# radio-a.net
KiCad netlist of a schematic drawn in Altium Designer
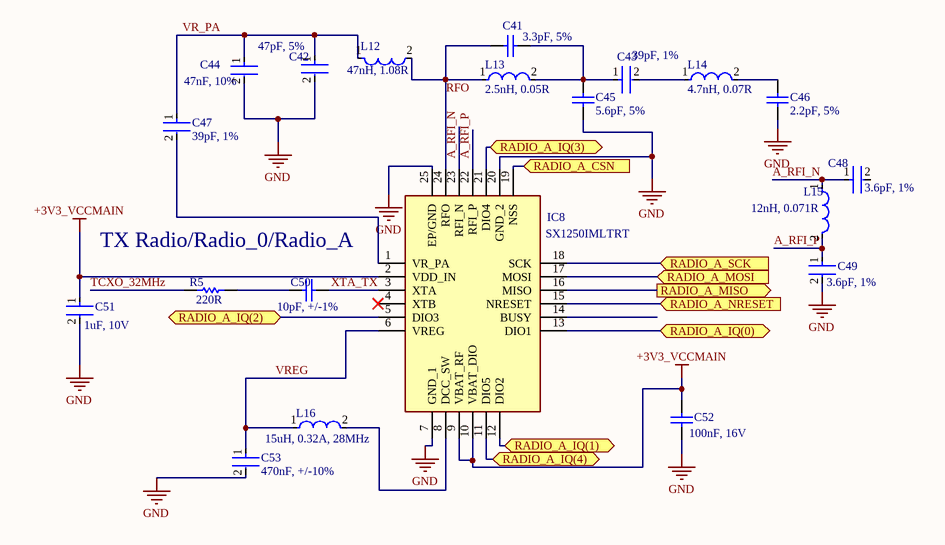
[diagram p0: radio-a.SchDoc]

(export (version "E")
  (design (tool "Eeschema 10.0.6"))
  (components
    (comp (ref "C41")
      (value "3.3pF, 5%")
      (footprint "CAPC0603(1608)100_L")
      (description "CAP 3.3pF 50V ±5% 0603 (1608 Metric) Thickness 1mm SMD")
      (fields (field (name "TOLERANCE") "Â±5%"))
      (libsource (lib "Altium Content Vault") (part "CAP"))
    )
    (comp (ref "C42")
      (value "47pF, 5%")
      (footprint "FP-GRM033-0_03-MFG")
      (description "Chip Multilayer Ceramic Capacitors for General Purpose, 0201, 47pF, C0G, 30ppm/°C, 5%, 50V")
      (fields (field (name "TOLERANCE") "5%") (field (name "VOLTAGE") "50V"))
      (libsource (lib "Altium Content Vault") (part "b4654b650e69147ec39a6b967a45e02"))
    )
    (comp (ref "C43")
      (value "39pF, 1%")
      (footprint "FP-GRM033-0_03-IPC_C")
      (description "Chip Multilayer Ceramic Capacitors for General Purpose, 0201, 39pF, C0G, 30ppm/°C, 1%, 50V")
      (libsource (lib "Altium Content Vault") (part "b4654b650e69147ec39a6b967a45e02"))
    )
    (comp (ref "C44")
      (value "47nF, 10%")
      (footprint "FP-GRM155-0_05-IPC_A")
      (description "Chip Multilayer Ceramic Capacitors for General Purpose, 0402, 47000pF, X7R, 15%, 10%, 16V")
      (fields (field (name "TOLERANCE") "10%") (field (name "VOLTAGE") "16V"))
      (libsource (lib "Altium Content Vault") (part "02cd4be3c70576c341d710602a673aa"))
    )
    (comp (ref "C45")
      (value "5.6pF, 5%")
      (footprint "CAPC1608X90X35ML15T15")
      (fields
        (field (name "MANUFACTURER") "AVX Interconnect / Elco")
        (field (name "PART NUMBER") "06035A5R6JAT2A")
      )
      (libsource (lib "Altium Content Vault") (part "CAP"))
    )
    (comp (ref "C46")
      (value "2.2pF, 5%")
      (footprint "CAPC1005X56X25NL10T15")
      (fields
        (field (name "MANUFACTURER") "AVX Interconnect / Elco")
        (field (name "PART NUMBER") "04025A2R2JAT2A")
      )
      (libsource (lib "Altium Content Vault") (part "CAP"))
    )
    (comp (ref "C47")
      (value "39pF, 1%")
      (footprint "FP-GRM033-0_03-IPC_C")
      (description "Chip Multilayer Ceramic Capacitors for General Purpose, 0201, 39pF, C0G, 30ppm/°C, 1%, 50V")
      (libsource (lib "Altium Content Vault") (part "b4654b650e69147ec39a6b967a45e02"))
    )
    (comp (ref "C48")
      (value "3.6pF, 1%")
      (footprint "FP-GJM033-0_03-IPC_C")
      (description "Ceramic Capacitor 3.6pF ±0.05pF 50V C0G 0201 (0603 Metric)")
      (libsource (lib "Altium Content Vault") (part "b4654b650e69147ec39a6b967a45e02"))
    )
    (comp (ref "C49")
      (value "3.6pF, 1%")
      (footprint "FP-GJM033-0_03-IPC_C")
      (description "Ceramic Capacitor 3.6pF ±0.05pF 50V C0G 0201 (0603 Metric)")
      (libsource (lib "Altium Content Vault") (part "b4654b650e69147ec39a6b967a45e02"))
    )
    (comp (ref "C50")
      (value "10pF, +/-1%")
      (footprint "CAPC2013X94X50NL20T25")
      (fields
        (field (name "MANUFACTURER") "AVX Interconnect / Elco")
        (field (name "PART NUMBER") "08055A100FAT2A")
      )
      (libsource (lib "Altium Content Vault") (part "CAP"))
    )
    (comp (ref "C51")
      (value "1uF, 10V")
      (footprint "FP-CC0805-0_85-MFG")
      (description "CAP CER 1UF 10V X5R 0805")
      (fields
        (field (name "TOLERANCE") "0.1")
        (field (name "OCTOPART") "https://octopart.com/cc0805kkx5r6bb105-yageo-9292777")
      )
      (libsource (lib "Altium Content Vault") (part "11868f565c42a9108669ba33697ecf6"))
    )
    (comp (ref "C52")
      (value "100nF, 16V")
      (footprint "CAPC1608X90X35LL15T15")
      (fields
        (field (name "PART NUMBER") "0603YC104MAT4A")
        (field (name "MANUFACTURER") "AVX Interconnect / Elco")
      )
      (libsource (lib "Altium Content Vault") (part "CAP"))
    )
    (comp (ref "C53")
      (value "470nF, +/-10%")
      (footprint "FP-CGA3E-0_3-0_1-MFG")
      (description "Cap Ceramic 470nF 25V X7R 10% Pad SMD 0603 +125°C Automotive T/R")
      (fields (field (name "TOLERANCE") "10%"))
      (libsource (lib "Altium Content Vault") (part "b4654b650e69147ec39a6b967a45e02"))
    )
    (comp (ref "IC8")
      (value "SX1250IMLTRT")
      (footprint "QFN50P400X400X100-25N-D")
      (description "Integrated Circuit")
      (fields (field (name "MOUSER PART NUMBER") "947-SX1250IMLTRT"))
      (libsource (lib "SamacSys") (part "SX1250IMLTRT"))
    )
    (comp (ref "L12")
      (value "47nH, 1.08R")
      (footprint "FP-LQW15AN_00-W0_5-0_1-MFG")
      (description "Wire Wound RF Inductor 47nH ±5% 210mA 1.08Ω 0402 (1005)")
      (fields (field (name "TOLERANCE") "5%"))
      (libsource (lib "") (part "725321dda6339637d4d059423bc1c3c_1"))
    )
    (comp (ref "L13")
      (value "2.5nH, 0.05R")
      (footprint "FP-LQW15AN_00-W0_6-0_1-MFG")
      (description "Wire Wound RF Inductor 2.5nH ±0.2nH 850mA 0.05Ω 0402 (1005)")
      (fields (field (name "TOLERANCE") "3%"))
      (libsource (lib "Altium Content Vault") (part "725321dda6339637d4d059423bc1c3c"))
    )
    (comp (ref "L14")
      (value "4.7nH, 0.07R")
      (footprint "FP-LQW15AN_00-W0_6-0_1-MFG")
      (description "Wire Wound RF Inductor 4.7nH ±0.2nH 750mA 0.07Ω 0402 (1005)")
      (libsource (lib "Altium Content Vault") (part "725321dda6339637d4d059423bc1c3c"))
    )
    (comp (ref "L15")
      (value "12nH, 0.071R")
      (footprint "FP-LQW18AN_10-MFG")
      (description "Wire Wound RF Inductor 12nH ±2% 750mA 0.071Ω 0603 (1608)")
      (fields (field (name "TOLERANCE") "2%"))
      (libsource (lib "Altium Content Vault") (part "725321dda6339637d4d059423bc1c3c"))
    )
    (comp (ref "L16")
      (value "15uH, 0.32A, 28MHz")
      (footprint "FP-CB2012-MFG")
      (description "SMD Inductors 15uH ±10% 0.32A 1.69Ω 0805")
      (fields (field (name "TOLERANCE") "10%"))
      (libsource (lib "Altium Content Vault") (part "725321dda6339637d4d059423bc1c3c"))
    )
    (comp (ref "R5")
      (value "220R")
      (footprint "RESC1608X55X30LL20T10")
      (fields (field (name "MANUFACTURER") "KOA Speer") (field (name "PART NUMBER") "RK73B1JTTD221J"))
      (libsource (lib "Altium Content Vault") (part "RES"))
    )
  )
  (nets
    (net (code "1") (name "+3V3_VCCMAIN") (class "Default")
      (node (ref "C51") (pin "1") (pinfunction "1_1") (pintype "passive"))
      (node (ref "C52") (pin "2") (pinfunction "2_2") (pintype "passive"))
      (node (ref "IC8") (pin "10") (pinfunction "VBAT_DIO_10") (pintype "passive"))
      (node (ref "IC8") (pin "2") (pinfunction "VDD_IN_2") (pintype "passive"))
      (node (ref "IC8") (pin "9") (pinfunction "VBAT_RF_9") (pintype "passive"))
    )
    (net (code "2") (name "/A_RFI_N") (class "Default")
      (node (ref "C48") (pin "1") (pinfunction "1_1") (pintype "passive"))
      (node (ref "IC8") (pin "23") (pinfunction "RFI_N_23") (pintype "passive"))
      (node (ref "L15") (pin "1") (pinfunction "1_1") (pintype "passive"))
    )
    (net (code "3") (name "/A_RFI_P") (class "Default")
      (node (ref "C49") (pin "1") (pinfunction "1_1") (pintype "passive"))
      (node (ref "IC8") (pin "22") (pinfunction "RFI_P_22") (pintype "passive"))
      (node (ref "L15") (pin "2") (pinfunction "2_2") (pintype "passive"))
    )
    (net (code "4") (name "/RADIO_A_CSN") (class "Default")
      (node (ref "IC8") (pin "19") (pinfunction "NSS_19") (pintype "passive"))
    )
    (net (code "5") (name "/RADIO_A_IQ(0)") (class "Default")
      (node (ref "IC8") (pin "13") (pinfunction "DIO1_13") (pintype "passive"))
    )
    (net (code "6") (name "/RADIO_A_IQ(1)") (class "Default")
      (node (ref "IC8") (pin "12") (pinfunction "DIO2_12") (pintype "passive"))
    )
    (net (code "7") (name "/RADIO_A_IQ(2)") (class "Default")
      (node (ref "IC8") (pin "5") (pinfunction "DIO3_5") (pintype "passive"))
    )
    (net (code "8") (name "/RADIO_A_IQ(3)") (class "Default")
      (node (ref "IC8") (pin "21") (pinfunction "DIO4_21") (pintype "passive"))
    )
    (net (code "9") (name "/RADIO_A_IQ(4)") (class "Default")
      (node (ref "IC8") (pin "11") (pinfunction "DIO5_11") (pintype "passive"))
    )
    (net (code "10") (name "/RADIO_A_MISO") (class "Default")
      (node (ref "IC8") (pin "16") (pinfunction "MISO_16") (pintype "passive"))
    )
    (net (code "11") (name "/RADIO_A_MOSI") (class "Default")
      (node (ref "IC8") (pin "17") (pinfunction "MOSI_17") (pintype "passive"))
    )
    (net (code "12") (name "/RADIO_A_NRESET") (class "Default")
      (node (ref "IC8") (pin "15") (pinfunction "NRESET_15") (pintype "passive"))
    )
    (net (code "13") (name "/RADIO_A_SCK") (class "Default")
      (node (ref "IC8") (pin "18") (pinfunction "SCK_18") (pintype "passive"))
    )
    (net (code "14") (name "/RFO") (class "Default")
      (node (ref "C41") (pin "2") (pinfunction "2_2") (pintype "passive"))
      (node (ref "IC8") (pin "24") (pinfunction "RFO_24") (pintype "passive"))
      (node (ref "L12") (pin "2") (pinfunction "2_2") (pintype "passive"))
      (node (ref "L13") (pin "1") (pinfunction "1_1") (pintype "passive"))
    )
    (net (code "15") (name "/TCXO_32MHz") (class "Default")
      (node (ref "R5") (pin "1") (pinfunction "1_1") (pintype "passive"))
    )
    (net (code "16") (name "/VREG") (class "Default")
      (node (ref "C53") (pin "1") (pinfunction "1_1") (pintype "passive"))
      (node (ref "IC8") (pin "6") (pinfunction "VREG_6") (pintype "passive"))
      (node (ref "L16") (pin "1") (pinfunction "1_1") (pintype "passive"))
    )
    (net (code "17") (name "/VR_PA") (class "Default")
      (node (ref "C42") (pin "1") (pinfunction "1_1") (pintype "passive"))
      (node (ref "C44") (pin "1") (pinfunction "1_1") (pintype "passive"))
      (node (ref "C47") (pin "1") (pinfunction "1_1") (pintype "passive"))
      (node (ref "L12") (pin "1") (pinfunction "1_1") (pintype "passive"))
    )
    (net (code "18") (name "/XTA_TX") (class "Default")
      (node (ref "C50") (pin "2") (pinfunction "2_2") (pintype "passive"))
      (node (ref "IC8") (pin "3") (pinfunction "XTA_3") (pintype "passive"))
    )
    (net (code "19") (name "GND") (class "Default")
      (node (ref "C42") (pin "2") (pinfunction "2_2") (pintype "passive"))
      (node (ref "C44") (pin "2") (pinfunction "2_2") (pintype "passive"))
      (node (ref "C45") (pin "1") (pinfunction "1_1") (pintype "passive"))
      (node (ref "C46") (pin "1") (pinfunction "1_1") (pintype "passive"))
      (node (ref "C49") (pin "2") (pinfunction "2_2") (pintype "passive"))
      (node (ref "C51") (pin "2") (pinfunction "2_2") (pintype "passive"))
      (node (ref "C52") (pin "1") (pinfunction "1_1") (pintype "passive"))
      (node (ref "C53") (pin "2") (pinfunction "2_2") (pintype "passive"))
      (node (ref "IC8") (pin "20") (pinfunction "GND_2_20") (pintype "passive"))
      (node (ref "IC8") (pin "25") (pinfunction "EP/GND_25") (pintype "passive"))
      (node (ref "IC8") (pin "7") (pinfunction "GND_1_7") (pintype "passive"))
    )
    (net (code "20") (name "Net-(C41-Pad1)") (class "Default")
      (node (ref "C41") (pin "1") (pinfunction "1_1") (pintype "passive"))
      (node (ref "C43") (pin "1") (pinfunction "1_1") (pintype "passive"))
      (node (ref "C45") (pin "2") (pinfunction "2_2") (pintype "passive"))
      (node (ref "L13") (pin "2") (pinfunction "2_2") (pintype "passive"))
    )
    (net (code "21") (name "Net-(C43-Pad2)") (class "Default")
      (node (ref "C43") (pin "2") (pinfunction "2_2") (pintype "passive"))
      (node (ref "L14") (pin "1") (pinfunction "1_1") (pintype "passive"))
    )
    (net (code "22") (name "Net-(C46-Pad2)") (class "Default")
      (node (ref "C46") (pin "2") (pinfunction "2_2") (pintype "passive"))
      (node (ref "L14") (pin "2") (pinfunction "2_2") (pintype "passive"))
    )
    (net (code "23") (name "Net-(C50-Pad1)") (class "Default")
      (node (ref "C50") (pin "1") (pinfunction "1_1") (pintype "passive"))
      (node (ref "R5") (pin "2") (pinfunction "2_2") (pintype "passive"))
    )
    (net (code "24") (name "Net-(IC8-DCC_SW)") (class "Default")
      (node (ref "IC8") (pin "8") (pinfunction "DCC_SW_8") (pintype "passive"))
      (node (ref "L16") (pin "2") (pinfunction "2_2") (pintype "passive"))
    )
    (net (code "25") (name "Net-(IC8-VR_PA)") (class "Default")
      (node (ref "C47") (pin "2") (pinfunction "2_2") (pintype "passive"))
      (node (ref "IC8") (pin "1") (pinfunction "VR_PA_1") (pintype "passive"))
    )
    (net (code "26") (name "unconnected-(C48-Pad2)") (class "Default")
      (node (ref "C48") (pin "2") (pinfunction "2_2") (pintype "passive"))
    )
    (net (code "27") (name "unconnected-(IC8-BUSY-Pad14)") (class "Default")
      (node (ref "IC8") (pin "14") (pinfunction "BUSY_14") (pintype "passive"))
    )
    (net (code "28") (name "unconnected-(IC8-XTB-Pad4)") (class "Default")
      (node (ref "IC8") (pin "4") (pinfunction "XTB_4") (pintype "passive+no_connect"))
    )
  )
)
